# hestiapiUS.net
KiCad netlist of a schematic drawn in EAGLE
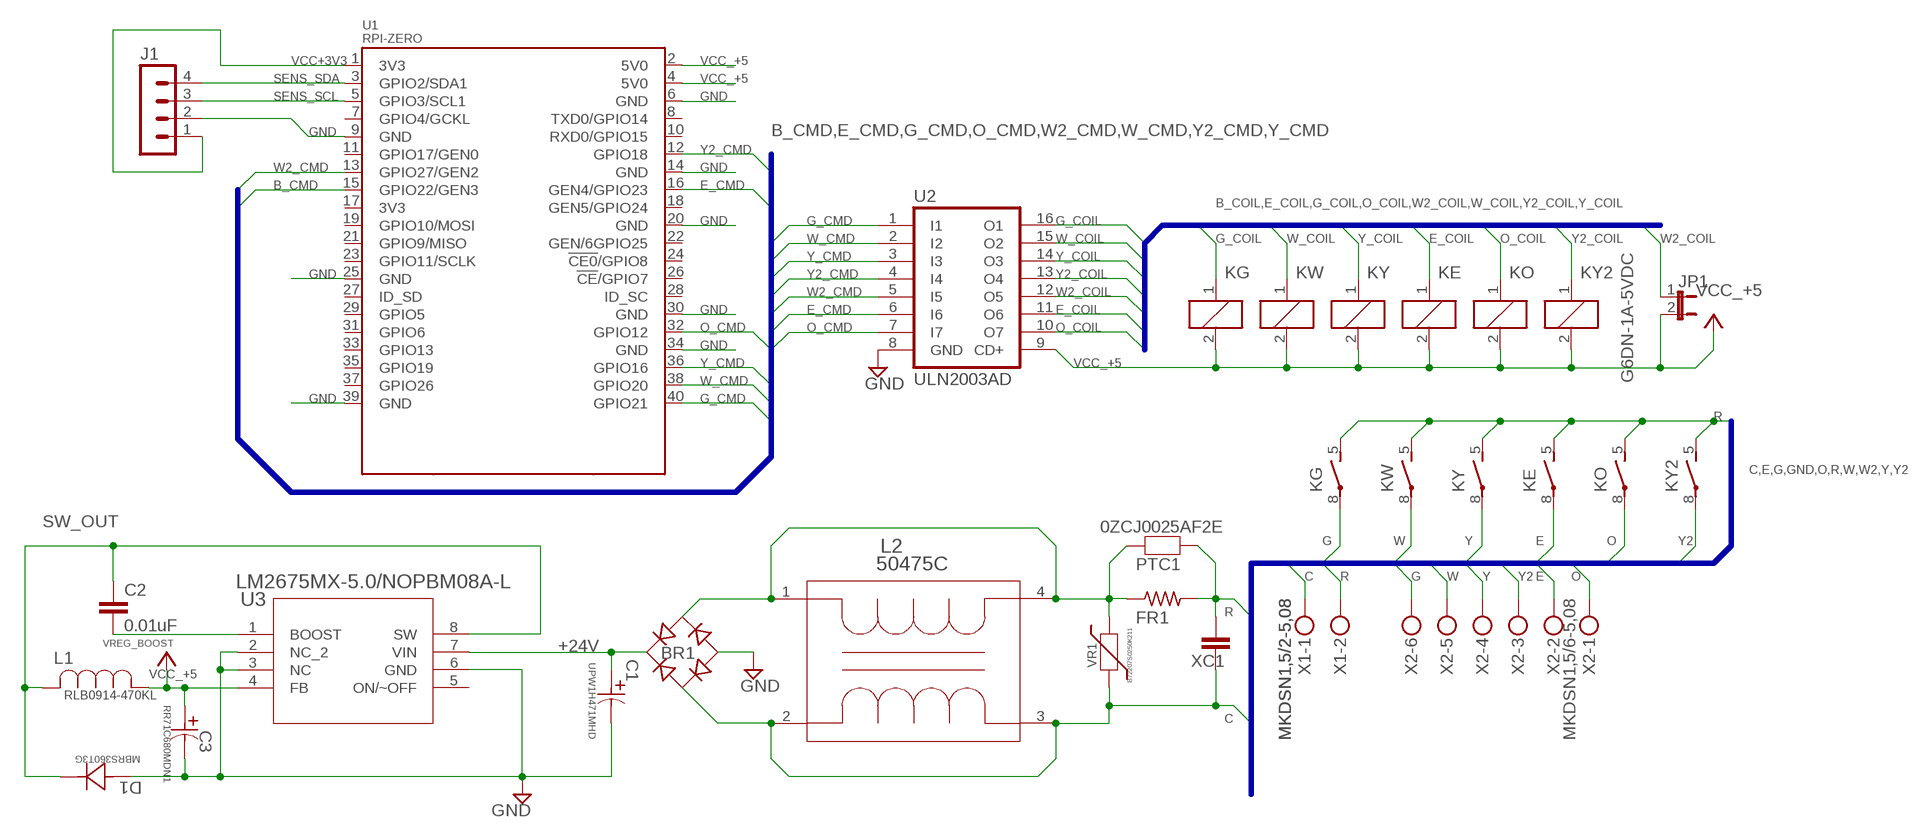
[diagram p0: schematic, sheet 1]

(export (version "E")
  (design (tool "Eeschema 10.0.6"))
  (components
    (comp (ref "BR1")
      (value "DF06S")
      (footprint "eagle-import:DFS")
      (libsource (lib "eagle-import") (part "DFS06"))
    )
    (comp (ref "C1")
      (value "UPW1H471MHD")
      (footprint "eagle-import:PCAP_12_5X20-THRU-ELECT")
      (libsource (lib "eagle-import") (part "UPW1H471MHD"))
    )
    (comp (ref "C2")
      (value "0.01uF")
      (footprint "eagle-import:0603")
      (libsource (lib "eagle-import") (part "0.01UF-0603-25V-(+80/-20%)"))
    )
    (comp (ref "C3")
      (value "RR71C680MDN1")
      (footprint "eagle-import:RR-A")
      (libsource (lib "eagle-import") (part "RR71C680MDN1"))
    )
    (comp (ref "D1")
      (value "MBRS360T3G")
      (footprint "eagle-import:DIODE_SMC_7P15X6P25")
      (libsource (lib "eagle-import") (part "MBRS360T3G"))
    )
    (comp (ref "FR1")
      (value "R-US_0207/12")
      (footprint "eagle-import:0207_12")
      (libsource (lib "eagle-import") (part "R-US_0207/12"))
    )
    (comp (ref "J1")
      (value "MA04-1")
      (footprint "eagle-import:MA04-1")
      (libsource (lib "eagle-import") (part "MA04-1"))
    )
    (comp (ref "JP1")
      (value "JP1E")
      (footprint "eagle-import:JP1")
      (libsource (lib "eagle-import") (part "JP1E"))
    )
    (comp (ref "KE")
      (value "G6DN-1A-5VDC")
      (footprint "eagle-import:G6DN")
      (libsource (lib "eagle-import") (part "G6DN?-1A-5VDC"))
    )
    (comp (ref "KG")
      (value "G6DN-1A-5VDC")
      (footprint "eagle-import:G6DN")
      (libsource (lib "eagle-import") (part "G6DN?-1A-5VDC"))
    )
    (comp (ref "KO")
      (value "G6DN-1A-5VDC")
      (footprint "eagle-import:G6DN")
      (libsource (lib "eagle-import") (part "G6DN?-1A-5VDC"))
    )
    (comp (ref "KW")
      (value "G6DN-1A-5VDC")
      (footprint "eagle-import:G6DN")
      (libsource (lib "eagle-import") (part "G6DN?-1A-5VDC"))
    )
    (comp (ref "KY")
      (value "G6DN-1A-5VDC")
      (footprint "eagle-import:G6DN")
      (libsource (lib "eagle-import") (part "G6DN?-1A-5VDC"))
    )
    (comp (ref "KY2")
      (value "G6DN-1A-5VDC")
      (footprint "eagle-import:G6DN")
      (libsource (lib "eagle-import") (part "G6DN?-1A-5VDC"))
    )
    (comp (ref "L1")
      (value "RLB0914-470KL")
      (footprint "eagle-import:IND_BOURNS_RLB0914")
      (fields (field (name "MANUFACTURER_PART_NUMBER") "RLB0914470KL"))
      (libsource (lib "eagle-import") (part "RLB0914-470KL"))
    )
    (comp (ref "L2")
      (value "50475C")
      (footprint "eagle-import:IND_50XXXC")
      (libsource (lib "eagle-import") (part "50475C"))
    )
    (comp (ref "PTC1")
      (value "0ZCJ0025AF2E")
      (footprint "eagle-import:0ZCJ")
      (libsource (lib "eagle-import") (part "0ZCJ0025AF2E"))
    )
    (comp (ref "U1")
      (value "RPI-ZERO")
      (footprint "eagle-import:RASPBERRYPI_BASTELSTUBE_V13_RASPI_BOARD_B+_FULL")
      (libsource (lib "eagle-import") (part "RPI-ZERO"))
    )
    (comp (ref "U2")
      (value "ULN2003AD")
      (footprint "eagle-import:SO16")
      (libsource (lib "eagle-import") (part "ULN2003AD"))
    )
    (comp (ref "U3")
      (value "LM2675MX-5.0/NOPBM08A-L")
      (footprint "eagle-import:M08A-L")
      (fields (field (name "MANUFACTURER_PART_NUMBER") "LM2675MX5.0NOPB"))
      (libsource (lib "eagle-import") (part "LM2675MX-5.0/NOPBM08A-L"))
    )
    (comp (ref "VR1")
      (value "B72207S0250K211")
      (footprint "eagle-import:VARISTOR7MM")
      (libsource (lib "eagle-import") (part "B72207S0250K211"))
    )
    (comp (ref "X1")
      (value "MKDSN1,5/2-5,08")
      (footprint "eagle-import:MKDSN1,5_2-5,08")
      (libsource (lib "eagle-import") (part "MKDSN1,5/2-5,08"))
    )
    (comp (ref "X2")
      (value "MKDSN1,5/6-5,08")
      (footprint "eagle-import:MKDSN1,5_6-5,08")
      (libsource (lib "eagle-import") (part "MKDSN1,5/6-5,08"))
    )
    (comp (ref "XC1")
      (value "C-EU025-024X044")
      (footprint "eagle-import:C025-024X044")
      (libsource (lib "eagle-import") (part "C-EU025-024X044"))
    )
  )
  (nets
    (net (code "3") (name "/+24V") (class "Default")
      (node (ref "BR1") (pin "+") (pinfunction "+_+") (pintype "passive"))
      (node (ref "C1") (pin "1") (pinfunction "1_1") (pintype "passive"))
      (node (ref "U3") (pin "7") (pinfunction "VIN_7") (pintype "input"))
    )
    (net (code "4") (name "/3V3") (class "Default")
      (node (ref "U1") (pin "17") (pinfunction "3V3_17") (pintype "power_in"))
    )
    (net (code "5") (name "/B_CMD") (class "Default")
      (node (ref "U1") (pin "15") (pinfunction "GPIO22/GEN3_15") (pintype "bidirectional"))
    )
    (net (code "6") (name "/C") (class "Default")
      (node (ref "BR1") (pin "AC1") (pinfunction "AC1_AC1") (pintype "passive"))
      (node (ref "L2") (pin "2") (pinfunction "2_2") (pintype "passive"))
      (node (ref "L2") (pin "3") (pinfunction "3_3") (pintype "passive"))
      (node (ref "VR1") (pin "1") (pinfunction "1_1") (pintype "passive"))
      (node (ref "X1") (pin "1") (pinfunction "KL_1") (pintype "passive"))
      (node (ref "XC1") (pin "2") (pinfunction "2_2") (pintype "passive"))
    )
    (net (code "7") (name "/E") (class "Default")
      (node (ref "KE") (pin "8") (pinfunction "P_8") (pintype "passive"))
      (node (ref "X2") (pin "2") (pinfunction "KL_2") (pintype "passive"))
    )
    (net (code "8") (name "/E_CMD") (class "Default")
      (node (ref "U1") (pin "16") (pinfunction "GEN4/GPIO23_16") (pintype "bidirectional"))
      (node (ref "U2") (pin "6") (pinfunction "I6_6") (pintype "input"))
    )
    (net (code "9") (name "/E_COIL") (class "Default")
      (node (ref "KE") (pin "1") (pinfunction "1_1") (pintype "passive"))
      (node (ref "U2") (pin "11") (pinfunction "O6_11") (pintype "open_collector"))
    )
    (net (code "10") (name "/G") (class "Default")
      (node (ref "KG") (pin "8") (pinfunction "P_8") (pintype "passive"))
      (node (ref "X2") (pin "6") (pinfunction "KL_6") (pintype "passive"))
    )
    (net (code "11") (name "/G_CMD") (class "Default")
      (node (ref "U1") (pin "40") (pinfunction "GPIO21_40") (pintype "bidirectional"))
      (node (ref "U2") (pin "1") (pinfunction "I1_1") (pintype "input"))
    )
    (net (code "12") (name "/G_COIL") (class "Default")
      (node (ref "KG") (pin "1") (pinfunction "1_1") (pintype "passive"))
      (node (ref "U2") (pin "16") (pinfunction "O1_16") (pintype "open_collector"))
    )
    (net (code "13") (name "/O") (class "Default")
      (node (ref "KO") (pin "8") (pinfunction "P_8") (pintype "passive"))
      (node (ref "X2") (pin "1") (pinfunction "KL_1") (pintype "passive"))
    )
    (net (code "14") (name "/O_CMD") (class "Default")
      (node (ref "U1") (pin "32") (pinfunction "GPIO12_32") (pintype "bidirectional"))
      (node (ref "U2") (pin "7") (pinfunction "I7_7") (pintype "input"))
    )
    (net (code "15") (name "/O_COIL") (class "Default")
      (node (ref "KO") (pin "1") (pinfunction "1_1") (pintype "passive"))
      (node (ref "U2") (pin "10") (pinfunction "O7_10") (pintype "open_collector"))
    )
    (net (code "16") (name "/R") (class "Default")
      (node (ref "FR1") (pin "2") (pinfunction "2_2") (pintype "passive"))
      (node (ref "KE") (pin "5") (pinfunction "S_5") (pintype "passive"))
      (node (ref "KG") (pin "5") (pinfunction "S_5") (pintype "passive"))
      (node (ref "KO") (pin "5") (pinfunction "S_5") (pintype "passive"))
      (node (ref "KW") (pin "5") (pinfunction "S_5") (pintype "passive"))
      (node (ref "KY") (pin "5") (pinfunction "S_5") (pintype "passive"))
      (node (ref "KY2") (pin "5") (pinfunction "S_5") (pintype "passive"))
      (node (ref "PTC1") (pin "2") (pinfunction "2_2") (pintype "passive"))
      (node (ref "X1") (pin "2") (pinfunction "KL_2") (pintype "passive"))
      (node (ref "XC1") (pin "1") (pinfunction "1_1") (pintype "passive"))
    )
    (net (code "17") (name "/SENS_SCL") (class "Default")
      (node (ref "J1") (pin "3") (pinfunction "3_3") (pintype "passive"))
      (node (ref "U1") (pin "5") (pinfunction "GPIO3/SCL1_5") (pintype "bidirectional"))
    )
    (net (code "18") (name "/SENS_SDA") (class "Default")
      (node (ref "J1") (pin "4") (pinfunction "4_4") (pintype "passive"))
      (node (ref "U1") (pin "3") (pinfunction "GPIO2/SDA1_3") (pintype "bidirectional"))
    )
    (net (code "19") (name "/SW_OUT") (class "Default")
      (node (ref "C2") (pin "1") (pinfunction "1_1") (pintype "passive"))
      (node (ref "D1") (pin "1") (pinfunction "1_1") (pintype "passive"))
      (node (ref "L1") (pin "2") (pinfunction "2_2") (pintype "passive"))
      (node (ref "U3") (pin "8") (pinfunction "SW_8") (pintype "output"))
    )
    (net (code "20") (name "/VCC+3V3") (class "Default")
      (node (ref "J1") (pin "1") (pinfunction "1_1") (pintype "passive"))
      (node (ref "U1") (pin "1") (pinfunction "3V3_1") (pintype "power_in"))
    )
    (net (code "21") (name "/VREG_BOOST") (class "Default")
      (node (ref "C2") (pin "2") (pinfunction "2_2") (pintype "passive"))
      (node (ref "U3") (pin "1") (pinfunction "BOOST_1") (pintype "passive"))
    )
    (net (code "22") (name "/W") (class "Default")
      (node (ref "KW") (pin "8") (pinfunction "P_8") (pintype "passive"))
      (node (ref "X2") (pin "5") (pinfunction "KL_5") (pintype "passive"))
    )
    (net (code "23") (name "/W2_CMD") (class "Default")
      (node (ref "U1") (pin "13") (pinfunction "GPIO27/GEN2_13") (pintype "bidirectional"))
      (node (ref "U2") (pin "5") (pinfunction "I5_5") (pintype "input"))
    )
    (net (code "24") (name "/W2_COIL") (class "Default")
      (node (ref "JP1") (pin "1") (pinfunction "1_1") (pintype "passive"))
      (node (ref "U2") (pin "12") (pinfunction "O5_12") (pintype "open_collector"))
    )
    (net (code "25") (name "/W_CMD") (class "Default")
      (node (ref "U1") (pin "38") (pinfunction "GPIO20_38") (pintype "bidirectional"))
      (node (ref "U2") (pin "2") (pinfunction "I2_2") (pintype "input"))
    )
    (net (code "26") (name "/W_COIL") (class "Default")
      (node (ref "KW") (pin "1") (pinfunction "1_1") (pintype "passive"))
      (node (ref "U2") (pin "15") (pinfunction "O2_15") (pintype "open_collector"))
    )
    (net (code "27") (name "/Y") (class "Default")
      (node (ref "KY") (pin "8") (pinfunction "P_8") (pintype "passive"))
      (node (ref "X2") (pin "4") (pinfunction "KL_4") (pintype "passive"))
    )
    (net (code "28") (name "/Y2") (class "Default")
      (node (ref "KY2") (pin "8") (pinfunction "P_8") (pintype "passive"))
      (node (ref "X2") (pin "3") (pinfunction "KL_3") (pintype "passive"))
    )
    (net (code "29") (name "/Y2_CMD") (class "Default")
      (node (ref "U1") (pin "12") (pinfunction "GPIO18_12") (pintype "bidirectional"))
      (node (ref "U2") (pin "4") (pinfunction "I4_4") (pintype "input"))
    )
    (net (code "30") (name "/Y2_COIL") (class "Default")
      (node (ref "KY2") (pin "1") (pinfunction "1_1") (pintype "passive"))
      (node (ref "U2") (pin "13") (pinfunction "O4_13") (pintype "open_collector"))
    )
    (net (code "31") (name "/Y_CMD") (class "Default")
      (node (ref "U1") (pin "36") (pinfunction "GPIO16_36") (pintype "bidirectional"))
      (node (ref "U2") (pin "3") (pinfunction "I3_3") (pintype "input"))
    )
    (net (code "32") (name "/Y_COIL") (class "Default")
      (node (ref "KY") (pin "1") (pinfunction "1_1") (pintype "passive"))
      (node (ref "U2") (pin "14") (pinfunction "O3_14") (pintype "open_collector"))
    )
    (net (code "36") (name "GND") (class "Default")
      (node (ref "BR1") (pin "-") (pinfunction "-_-") (pintype "passive"))
      (node (ref "C1") (pin "2") (pinfunction "2_2") (pintype "passive"))
      (node (ref "C3") (pin "2") (pinfunction "2_2") (pintype "passive"))
      (node (ref "D1") (pin "2") (pinfunction "2_2") (pintype "passive"))
      (node (ref "J1") (pin "2") (pinfunction "2_2") (pintype "passive"))
      (node (ref "U1") (pin "14") (pinfunction "GND_14") (pintype "power_in"))
      (node (ref "U1") (pin "20") (pinfunction "GND_20") (pintype "power_in"))
      (node (ref "U1") (pin "25") (pinfunction "GND_25") (pintype "power_in"))
      (node (ref "U1") (pin "30") (pinfunction "GND_30") (pintype "power_in"))
      (node (ref "U1") (pin "34") (pinfunction "GND_34") (pintype "power_in"))
      (node (ref "U1") (pin "39") (pinfunction "GND_39") (pintype "power_in"))
      (node (ref "U1") (pin "6") (pinfunction "GND_6") (pintype "power_in"))
      (node (ref "U1") (pin "9") (pinfunction "GND_9") (pintype "power_in"))
      (node (ref "U2") (pin "8") (pinfunction "GND_8") (pintype "power_in"))
      (node (ref "U3") (pin "2") (pinfunction "NC_2_2") (pintype "passive"))
      (node (ref "U3") (pin "3") (pinfunction "NC_3") (pintype "passive"))
      (node (ref "U3") (pin "6") (pinfunction "GND_6") (pintype "passive"))
    )
    (net (code "37") (name "Net-(BR1-PadAC2)") (class "Default")
      (node (ref "BR1") (pin "AC2") (pinfunction "AC2_AC2") (pintype "passive"))
      (node (ref "FR1") (pin "1") (pinfunction "1_1") (pintype "passive"))
      (node (ref "L2") (pin "1") (pinfunction "1_1") (pintype "passive"))
      (node (ref "L2") (pin "4") (pinfunction "4_4") (pintype "passive"))
      (node (ref "PTC1") (pin "1") (pinfunction "1_1") (pintype "passive"))
      (node (ref "VR1") (pin "2") (pinfunction "2_2") (pintype "passive"))
    )
    (net (code "38") (name "VCC") (class "Default")
      (node (ref "C3") (pin "1") (pinfunction "1_1") (pintype "passive"))
      (node (ref "JP1") (pin "2") (pinfunction "2_2") (pintype "passive"))
      (node (ref "KE") (pin "2") (pinfunction "2_2") (pintype "passive"))
      (node (ref "KG") (pin "2") (pinfunction "2_2") (pintype "passive"))
      (node (ref "KO") (pin "2") (pinfunction "2_2") (pintype "passive"))
      (node (ref "KW") (pin "2") (pinfunction "2_2") (pintype "passive"))
      (node (ref "KY") (pin "2") (pinfunction "2_2") (pintype "passive"))
      (node (ref "KY2") (pin "2") (pinfunction "2_2") (pintype "passive"))
      (node (ref "L1") (pin "1") (pinfunction "1_1") (pintype "passive"))
      (node (ref "U1") (pin "2") (pinfunction "5V0_2") (pintype "power_in"))
      (node (ref "U1") (pin "4") (pinfunction "5V0_4") (pintype "power_in"))
      (node (ref "U2") (pin "9") (pinfunction "CD+_9") (pintype "passive"))
      (node (ref "U3") (pin "4") (pinfunction "FB_4") (pintype "passive"))
    )
    (net (code "39") (name "unconnected-(U1-GEN5{slash}GPIO24-Pad18)") (class "Default")
      (node (ref "U1") (pin "18") (pinfunction "GEN5/GPIO24_18") (pintype "bidirectional"))
    )
    (net (code "40") (name "unconnected-(U1-GEN{slash}6GPIO25-Pad22)") (class "Default")
      (node (ref "U1") (pin "22") (pinfunction "GEN/6GPIO25_22") (pintype "bidirectional"))
    )
    (net (code "41") (name "unconnected-(U1-GPIO4{slash}GCKL-Pad7)") (class "Default")
      (node (ref "U1") (pin "7") (pinfunction "GPIO4/GCKL_7") (pintype "bidirectional"))
    )
    (net (code "42") (name "unconnected-(U1-GPIO5-Pad29)") (class "Default")
      (node (ref "U1") (pin "29") (pinfunction "GPIO5_29") (pintype "bidirectional"))
    )
    (net (code "43") (name "unconnected-(U1-GPIO6-Pad31)") (class "Default")
      (node (ref "U1") (pin "31") (pinfunction "GPIO6_31") (pintype "bidirectional"))
    )
    (net (code "44") (name "unconnected-(U1-GPIO9{slash}MISO-Pad21)") (class "Default")
      (node (ref "U1") (pin "21") (pinfunction "GPIO9/MISO_21") (pintype "bidirectional"))
    )
    (net (code "45") (name "unconnected-(U1-GPIO10{slash}MOSI-Pad19)") (class "Default")
      (node (ref "U1") (pin "19") (pinfunction "GPIO10/MOSI_19") (pintype "bidirectional"))
    )
    (net (code "46") (name "unconnected-(U1-GPIO11{slash}SCLK-Pad23)") (class "Default")
      (node (ref "U1") (pin "23") (pinfunction "GPIO11/SCLK_23") (pintype "bidirectional"))
    )
    (net (code "47") (name "unconnected-(U1-GPIO13-Pad33)") (class "Default")
      (node (ref "U1") (pin "33") (pinfunction "GPIO13_33") (pintype "bidirectional"))
    )
    (net (code "48") (name "unconnected-(U1-GPIO17{slash}GEN0-Pad11)") (class "Default")
      (node (ref "U1") (pin "11") (pinfunction "GPIO17/GEN0_11") (pintype "bidirectional"))
    )
    (net (code "49") (name "unconnected-(U1-GPIO19-Pad35)") (class "Default")
      (node (ref "U1") (pin "35") (pinfunction "GPIO19_35") (pintype "bidirectional"))
    )
    (net (code "50") (name "unconnected-(U1-GPIO26-Pad37)") (class "Default")
      (node (ref "U1") (pin "37") (pinfunction "GPIO26_37") (pintype "bidirectional"))
    )
    (net (code "51") (name "unconnected-(U1-ID_SC-Pad28)") (class "Default")
      (node (ref "U1") (pin "28") (pinfunction "ID_SC_28") (pintype "bidirectional"))
    )
    (net (code "52") (name "unconnected-(U1-ID_SD-Pad27)") (class "Default")
      (node (ref "U1") (pin "27") (pinfunction "ID_SD_27") (pintype "bidirectional"))
    )
    (net (code "53") (name "unconnected-(U1-RXD0{slash}GPIO15-Pad10)") (class "Default")
      (node (ref "U1") (pin "10") (pinfunction "RXD0/GPIO15_10") (pintype "bidirectional"))
    )
    (net (code "54") (name "unconnected-(U1-TXD0{slash}GPIO14-Pad8)") (class "Default")
      (node (ref "U1") (pin "8") (pinfunction "TXD0/GPIO14_8") (pintype "bidirectional"))
    )
    (net (code "55") (name "unconnected-(U1-~{CE0}{slash}GPIO8-Pad24)") (class "Default")
      (node (ref "U1") (pin "24") (pinfunction "~{CE0}/GPIO8_24") (pintype "bidirectional"))
    )
    (net (code "56") (name "unconnected-(U1-~{CE}{slash}GPIO7-Pad26)") (class "Default")
      (node (ref "U1") (pin "26") (pinfunction "~{CE}/GPIO7_26") (pintype "bidirectional"))
    )
    (net (code "57") (name "unconnected-(U3-ON{slash}~{OFF}-Pad5)") (class "Default")
      (node (ref "U3") (pin "5") (pinfunction "ON/~{OFF}_5") (pintype "passive"))
    )
  )
)
